# ir_remote_v3.net
KiCad netlist of a schematic drawn in EAGLE
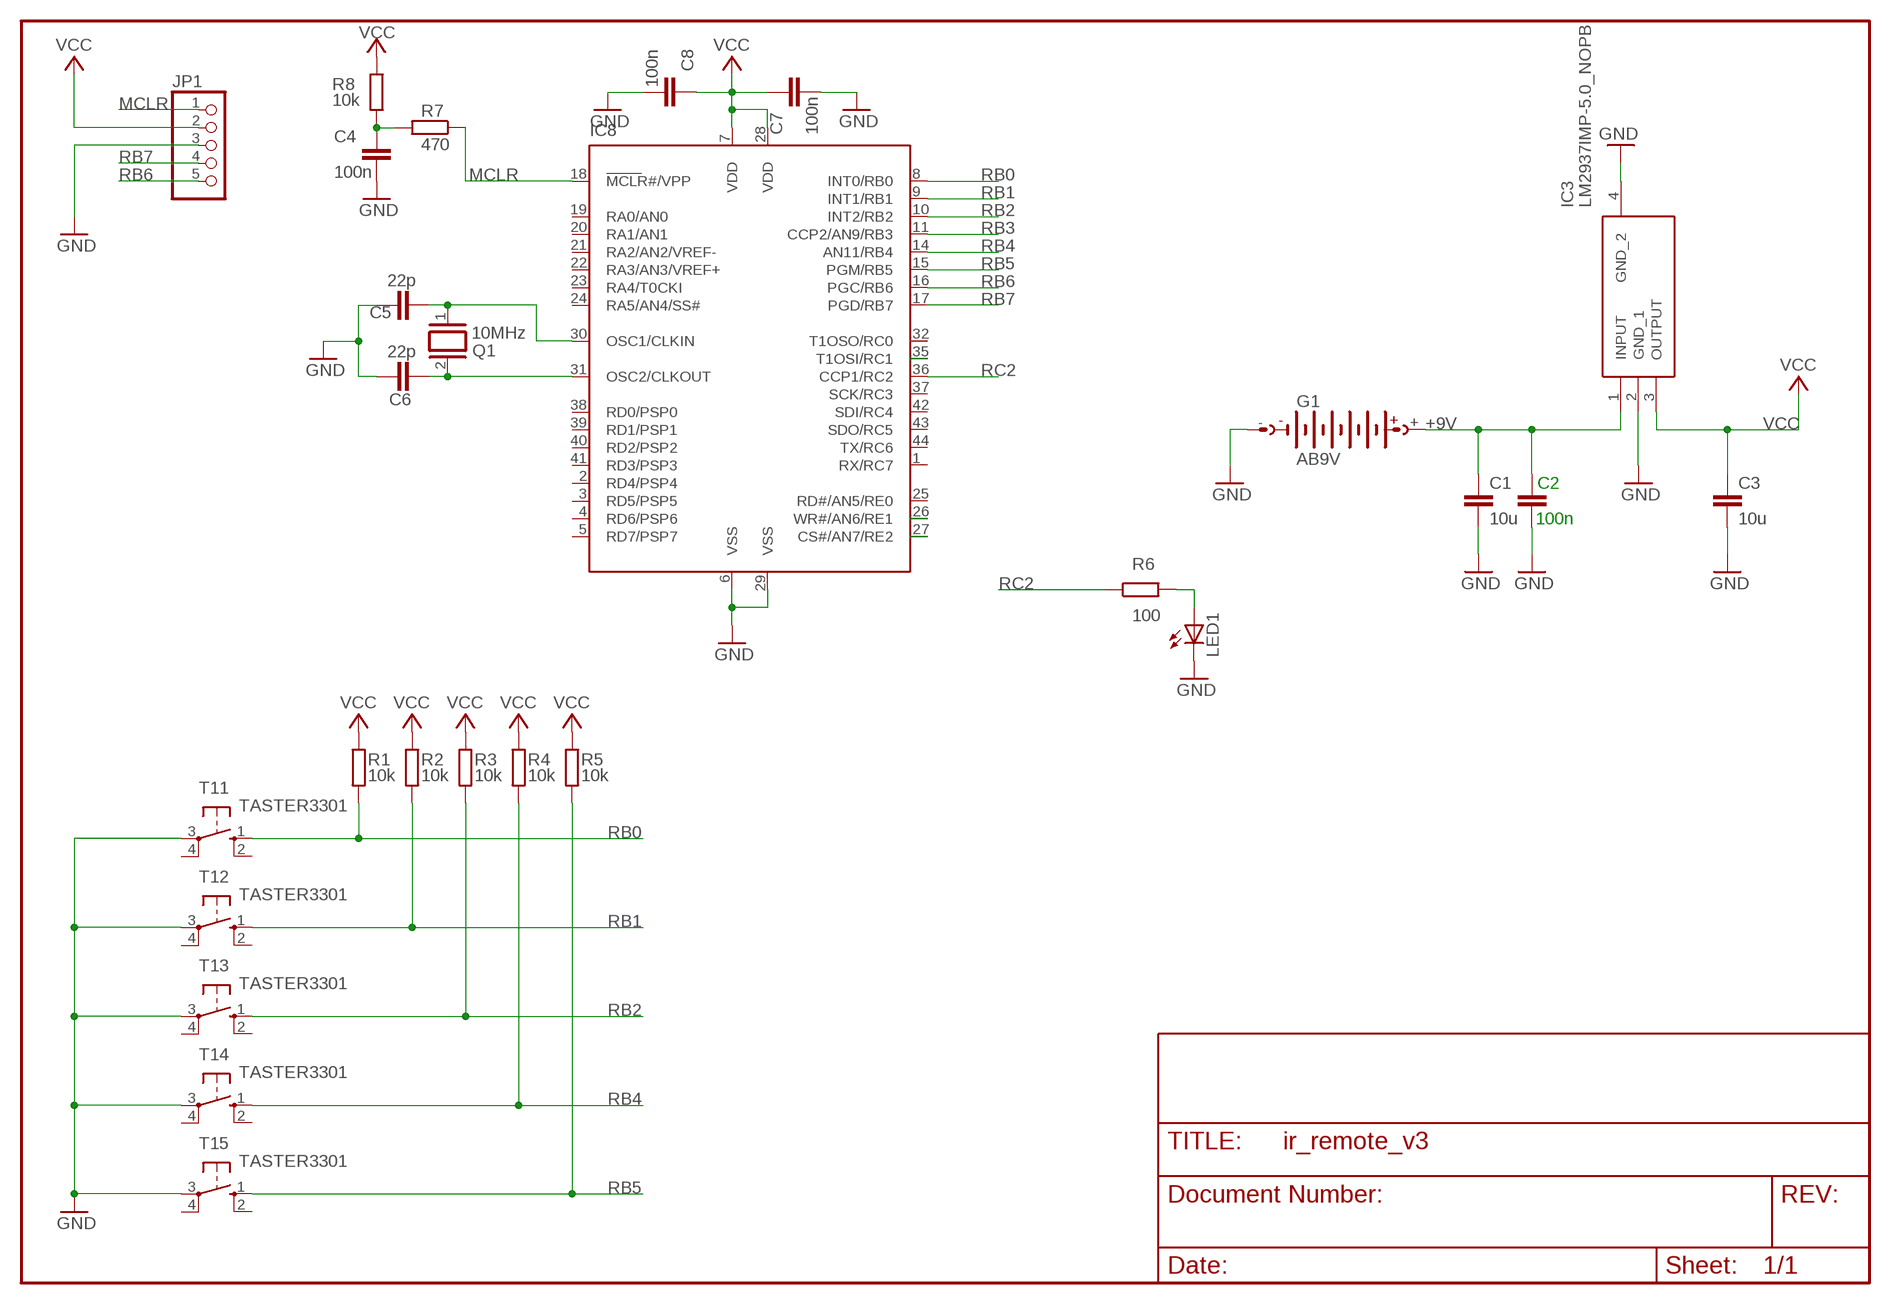
[diagram p0: schematic, sheet 1]

(export (version "E")
  (design (tool "Eeschema 10.0.6"))
  (components
    (comp (ref "C1")
      (value "10u")
      (footprint "eagle-import:C0805")
      (libsource (lib "eagle-import") (part "C-EUC0805"))
    )
    (comp (ref "C2")
      (value "100n")
      (footprint "eagle-import:C0805")
      (libsource (lib "eagle-import") (part "rcl_416_C-EUC0805"))
    )
    (comp (ref "C3")
      (value "10u")
      (footprint "eagle-import:C0805")
      (libsource (lib "eagle-import") (part "C-EUC0805"))
    )
    (comp (ref "C4")
      (value "100n")
      (footprint "eagle-import:C0805")
      (libsource (lib "eagle-import") (part "C-EUC0805"))
    )
    (comp (ref "C5")
      (value "22p")
      (footprint "eagle-import:C0603_WE")
      (libsource (lib "eagle-import") (part "C-EUC0603_WE"))
    )
    (comp (ref "C6")
      (value "22p")
      (footprint "eagle-import:C0603_WE")
      (libsource (lib "eagle-import") (part "C-EUC0603_WE"))
    )
    (comp (ref "C7")
      (value "100n")
      (footprint "eagle-import:C0805")
      (libsource (lib "eagle-import") (part "C-EUC0805"))
    )
    (comp (ref "C8")
      (value "100n")
      (footprint "eagle-import:C0805")
      (libsource (lib "eagle-import") (part "C-EUC0805"))
    )
    (comp (ref "G1")
      (value "AB9V")
      (footprint "eagle-import:AB9V")
      (libsource (lib "eagle-import") (part "AB9V"))
    )
    (comp (ref "IC3")
      (value "LM2937IMP-5.0_NOPB")
      (footprint "eagle-import:SOT230P700X180-4N")
      (fields (field (name "MANUFACTURER_PART_NUMBER") "LM2937IMP-5.0/NOPB"))
      (libsource (lib "eagle-import") (part "LM2937IMP-5.0_NOPB"))
    )
    (comp (ref "IC8")
      (value "PIC18F4520")
      (footprint "eagle-import:TQFP44")
      (libsource (lib "eagle-import") (part "PIC18F4520"))
    )
    (comp (ref "JP1")
      (value "PINHD-1X5")
      (footprint "eagle-import:1X05")
      (libsource (lib "eagle-import") (part "PINHD-1X5"))
    )
    (comp (ref "LED1")
      (value "LED5MM")
      (footprint "eagle-import:LED5MM")
      (libsource (lib "eagle-import") (part "LED5MM"))
    )
    (comp (ref "Q1")
      (value "10MHz")
      (footprint "eagle-import:QUARZ_HC5032_2")
      (libsource (lib "eagle-import") (part "XTAL_HC5032"))
    )
    (comp (ref "R1")
      (value "10k")
      (footprint "eagle-import:M0805")
      (libsource (lib "eagle-import") (part "R-EU_M0805"))
    )
    (comp (ref "R2")
      (value "10k")
      (footprint "eagle-import:M0805")
      (libsource (lib "eagle-import") (part "R-EU_M0805"))
    )
    (comp (ref "R3")
      (value "10k")
      (footprint "eagle-import:M0805")
      (libsource (lib "eagle-import") (part "R-EU_M0805"))
    )
    (comp (ref "R4")
      (value "10k")
      (footprint "eagle-import:M0805")
      (libsource (lib "eagle-import") (part "R-EU_M0805"))
    )
    (comp (ref "R5")
      (value "10k")
      (footprint "eagle-import:M0805")
      (libsource (lib "eagle-import") (part "R-EU_M0805"))
    )
    (comp (ref "R6")
      (value "100")
      (footprint "eagle-import:M0805")
      (libsource (lib "eagle-import") (part "R-EU_M0805"))
    )
    (comp (ref "R7")
      (value "470")
      (footprint "eagle-import:M0805")
      (libsource (lib "eagle-import") (part "R-EU_M0805"))
    )
    (comp (ref "R8")
      (value "10k")
      (footprint "eagle-import:M0805")
      (libsource (lib "eagle-import") (part "R-EU_M0805"))
    )
    (comp (ref "T11")
      (value "TASTER3301")
      (footprint "eagle-import:TASTER3301")
      (libsource (lib "eagle-import") (part "TASTER3301"))
    )
    (comp (ref "T12")
      (value "TASTER3301")
      (footprint "eagle-import:TASTER3301")
      (libsource (lib "eagle-import") (part "TASTER3301"))
    )
    (comp (ref "T13")
      (value "TASTER3301")
      (footprint "eagle-import:TASTER3301")
      (libsource (lib "eagle-import") (part "TASTER3301"))
    )
    (comp (ref "T14")
      (value "TASTER3301")
      (footprint "eagle-import:TASTER3301")
      (libsource (lib "eagle-import") (part "TASTER3301"))
    )
    (comp (ref "T15")
      (value "TASTER3301")
      (footprint "eagle-import:TASTER3301")
      (libsource (lib "eagle-import") (part "TASTER3301"))
    )
  )
  (nets
    (net (code "1") (name "/+9V") (class "Default")
      (node (ref "C1") (pin "1") (pinfunction "1_1") (pintype "passive"))
      (node (ref "C2") (pin "1") (pinfunction "1_1") (pintype "passive"))
      (node (ref "G1") (pin "+") (pinfunction "+_+") (pintype "passive"))
      (node (ref "IC3") (pin "1") (pinfunction "INPUT_1") (pintype "bidirectional"))
    )
    (net (code "2") (name "/MCLR") (class "Default")
      (node (ref "IC8") (pin "18") (pinfunction "MCLR#/VPP_18") (pintype "input"))
      (node (ref "JP1") (pin "1") (pinfunction "1_1") (pintype "passive"))
      (node (ref "R7") (pin "1") (pinfunction "1_1") (pintype "passive"))
    )
    (net (code "3") (name "/RB0") (class "Default")
      (node (ref "IC8") (pin "8") (pinfunction "INT0/RB0_8") (pintype "bidirectional"))
      (node (ref "R1") (pin "2") (pinfunction "2_2") (pintype "passive"))
      (node (ref "T11") (pin "1") (pinfunction "S_1") (pintype "passive"))
    )
    (net (code "4") (name "/RB1") (class "Default")
      (node (ref "IC8") (pin "35") (pinfunction "T1OSI/RC1_35") (pintype "bidirectional"))
      (node (ref "IC8") (pin "9") (pinfunction "INT1/RB1_9") (pintype "bidirectional"))
      (node (ref "R2") (pin "2") (pinfunction "2_2") (pintype "passive"))
      (node (ref "T12") (pin "1") (pinfunction "S_1") (pintype "passive"))
    )
    (net (code "5") (name "/RB2") (class "Default")
      (node (ref "IC8") (pin "10") (pinfunction "INT2/RB2_10") (pintype "bidirectional"))
      (node (ref "IC8") (pin "32") (pinfunction "T1OSO/RC0_32") (pintype "bidirectional"))
      (node (ref "R3") (pin "2") (pinfunction "2_2") (pintype "passive"))
      (node (ref "T13") (pin "1") (pinfunction "S_1") (pintype "passive"))
    )
    (net (code "6") (name "/RB3") (class "Default")
      (node (ref "IC8") (pin "11") (pinfunction "CCP2/AN9/RB3_11") (pintype "bidirectional"))
    )
    (net (code "7") (name "/RB4") (class "Default")
      (node (ref "IC8") (pin "14") (pinfunction "AN11/RB4_14") (pintype "bidirectional"))
      (node (ref "R4") (pin "2") (pinfunction "2_2") (pintype "passive"))
      (node (ref "T14") (pin "1") (pinfunction "S_1") (pintype "passive"))
    )
    (net (code "8") (name "/RB5") (class "Default")
      (node (ref "IC8") (pin "15") (pinfunction "PGM/RB5_15") (pintype "bidirectional"))
      (node (ref "R5") (pin "2") (pinfunction "2_2") (pintype "passive"))
      (node (ref "T15") (pin "1") (pinfunction "S_1") (pintype "passive"))
    )
    (net (code "9") (name "/RB6") (class "Default")
      (node (ref "IC8") (pin "16") (pinfunction "PGC/RB6_16") (pintype "bidirectional"))
      (node (ref "JP1") (pin "5") (pinfunction "5_5") (pintype "passive"))
    )
    (net (code "10") (name "/RB7") (class "Default")
      (node (ref "IC8") (pin "17") (pinfunction "PGD/RB7_17") (pintype "bidirectional"))
      (node (ref "JP1") (pin "4") (pinfunction "4_4") (pintype "passive"))
    )
    (net (code "11") (name "/RC2") (class "Default")
      (node (ref "IC8") (pin "36") (pinfunction "CCP1/RC2_36") (pintype "bidirectional"))
      (node (ref "R6") (pin "1") (pinfunction "1_1") (pintype "passive"))
    )
    (net (code "12") (name "GND") (class "Default")
      (node (ref "C1") (pin "2") (pinfunction "2_2") (pintype "passive"))
      (node (ref "C2") (pin "2") (pinfunction "2_2") (pintype "passive"))
      (node (ref "C3") (pin "2") (pinfunction "2_2") (pintype "passive"))
      (node (ref "C4") (pin "2") (pinfunction "2_2") (pintype "passive"))
      (node (ref "C5") (pin "1") (pinfunction "1_1") (pintype "passive"))
      (node (ref "C6") (pin "1") (pinfunction "1_1") (pintype "passive"))
      (node (ref "C7") (pin "2") (pinfunction "2_2") (pintype "passive"))
      (node (ref "C8") (pin "2") (pinfunction "2_2") (pintype "passive"))
      (node (ref "G1") (pin "-") (pinfunction "-_-") (pintype "passive"))
      (node (ref "IC3") (pin "2") (pinfunction "GND_1_2") (pintype "bidirectional"))
      (node (ref "IC3") (pin "4") (pinfunction "GND_2_4") (pintype "bidirectional"))
      (node (ref "IC8") (pin "29") (pinfunction "VSS_29") (pintype "bidirectional"))
      (node (ref "IC8") (pin "6") (pinfunction "VSS_6") (pintype "bidirectional"))
      (node (ref "JP1") (pin "3") (pinfunction "3_3") (pintype "passive"))
      (node (ref "LED1") (pin "K") (pinfunction "C_K") (pintype "passive"))
      (node (ref "T11") (pin "3") (pinfunction "P_3") (pintype "passive"))
      (node (ref "T12") (pin "3") (pinfunction "P_3") (pintype "passive"))
      (node (ref "T13") (pin "3") (pinfunction "P_3") (pintype "passive"))
      (node (ref "T14") (pin "3") (pinfunction "P_3") (pintype "passive"))
      (node (ref "T15") (pin "3") (pinfunction "P_3") (pintype "passive"))
    )
    (net (code "13") (name "Net-(C4-Pad1)") (class "Default")
      (node (ref "C4") (pin "1") (pinfunction "1_1") (pintype "passive"))
      (node (ref "R7") (pin "2") (pinfunction "2_2") (pintype "passive"))
      (node (ref "R8") (pin "2") (pinfunction "2_2") (pintype "passive"))
    )
    (net (code "14") (name "Net-(IC8-OSC1{slash}CLKIN)") (class "Default")
      (node (ref "C5") (pin "2") (pinfunction "2_2") (pintype "passive"))
      (node (ref "IC8") (pin "30") (pinfunction "OSC1/CLKIN_30") (pintype "input"))
      (node (ref "Q1") (pin "1") (pinfunction "1_1") (pintype "passive"))
    )
    (net (code "15") (name "Net-(IC8-OSC2{slash}CLKOUT)") (class "Default")
      (node (ref "C6") (pin "2") (pinfunction "2_2") (pintype "passive"))
      (node (ref "IC8") (pin "31") (pinfunction "OSC2/CLKOUT_31") (pintype "output"))
      (node (ref "Q1") (pin "2") (pinfunction "2_2") (pintype "passive"))
    )
    (net (code "16") (name "Net-(LED1-PadA)") (class "Default")
      (node (ref "LED1") (pin "A") (pinfunction "A_A") (pintype "passive"))
      (node (ref "R6") (pin "2") (pinfunction "2_2") (pintype "passive"))
    )
    (net (code "17") (name "VCC") (class "Default")
      (node (ref "C3") (pin "1") (pinfunction "1_1") (pintype "passive"))
      (node (ref "C7") (pin "1") (pinfunction "1_1") (pintype "passive"))
      (node (ref "C8") (pin "1") (pinfunction "1_1") (pintype "passive"))
      (node (ref "IC3") (pin "3") (pinfunction "OUTPUT_3") (pintype "bidirectional"))
      (node (ref "IC8") (pin "28") (pinfunction "VDD_28") (pintype "bidirectional"))
      (node (ref "IC8") (pin "7") (pinfunction "VDD_7") (pintype "bidirectional"))
      (node (ref "JP1") (pin "2") (pinfunction "2_2") (pintype "passive"))
      (node (ref "R1") (pin "1") (pinfunction "1_1") (pintype "passive"))
      (node (ref "R2") (pin "1") (pinfunction "1_1") (pintype "passive"))
      (node (ref "R3") (pin "1") (pinfunction "1_1") (pintype "passive"))
      (node (ref "R4") (pin "1") (pinfunction "1_1") (pintype "passive"))
      (node (ref "R5") (pin "1") (pinfunction "1_1") (pintype "passive"))
      (node (ref "R8") (pin "1") (pinfunction "1_1") (pintype "passive"))
    )
    (net (code "18") (name "unconnected-(IC8-CS#{slash}AN7{slash}RE2-Pad27)") (class "Default")
      (node (ref "IC8") (pin "27") (pinfunction "CS#/AN7/RE2_27") (pintype "bidirectional"))
    )
    (net (code "19") (name "unconnected-(IC8-RA0{slash}AN0-Pad19)") (class "Default")
      (node (ref "IC8") (pin "19") (pinfunction "RA0/AN0_19") (pintype "bidirectional"))
    )
    (net (code "20") (name "unconnected-(IC8-RA1{slash}AN1-Pad20)") (class "Default")
      (node (ref "IC8") (pin "20") (pinfunction "RA1/AN1_20") (pintype "bidirectional"))
    )
    (net (code "21") (name "unconnected-(IC8-RA2{slash}AN2{slash}VREF--Pad21)") (class "Default")
      (node (ref "IC8") (pin "21") (pinfunction "RA2/AN2/VREF-_21") (pintype "bidirectional"))
    )
    (net (code "22") (name "unconnected-(IC8-RA3{slash}AN3{slash}VREF+-Pad22)") (class "Default")
      (node (ref "IC8") (pin "22") (pinfunction "RA3/AN3/VREF+_22") (pintype "bidirectional"))
    )
    (net (code "23") (name "unconnected-(IC8-RA4{slash}T0CKI-Pad23)") (class "Default")
      (node (ref "IC8") (pin "23") (pinfunction "RA4/T0CKI_23") (pintype "bidirectional"))
    )
    (net (code "24") (name "unconnected-(IC8-RA5{slash}AN4{slash}SS#-Pad24)") (class "Default")
      (node (ref "IC8") (pin "24") (pinfunction "RA5/AN4/SS#_24") (pintype "bidirectional"))
    )
    (net (code "25") (name "unconnected-(IC8-RD#{slash}AN5{slash}RE0-Pad25)") (class "Default")
      (node (ref "IC8") (pin "25") (pinfunction "RD#/AN5/RE0_25") (pintype "bidirectional"))
    )
    (net (code "26") (name "unconnected-(IC8-RD0{slash}PSP0-Pad38)") (class "Default")
      (node (ref "IC8") (pin "38") (pinfunction "RD0/PSP0_38") (pintype "bidirectional"))
    )
    (net (code "27") (name "unconnected-(IC8-RD1{slash}PSP1-Pad39)") (class "Default")
      (node (ref "IC8") (pin "39") (pinfunction "RD1/PSP1_39") (pintype "bidirectional"))
    )
    (net (code "28") (name "unconnected-(IC8-RD2{slash}PSP2-Pad40)") (class "Default")
      (node (ref "IC8") (pin "40") (pinfunction "RD2/PSP2_40") (pintype "bidirectional"))
    )
    (net (code "29") (name "unconnected-(IC8-RD3{slash}PSP3-Pad41)") (class "Default")
      (node (ref "IC8") (pin "41") (pinfunction "RD3/PSP3_41") (pintype "bidirectional"))
    )
    (net (code "30") (name "unconnected-(IC8-RD4{slash}PSP4-Pad2)") (class "Default")
      (node (ref "IC8") (pin "2") (pinfunction "RD4/PSP4_2") (pintype "bidirectional"))
    )
    (net (code "31") (name "unconnected-(IC8-RD5{slash}PSP5-Pad3)") (class "Default")
      (node (ref "IC8") (pin "3") (pinfunction "RD5/PSP5_3") (pintype "bidirectional"))
    )
    (net (code "32") (name "unconnected-(IC8-RD6{slash}PSP6-Pad4)") (class "Default")
      (node (ref "IC8") (pin "4") (pinfunction "RD6/PSP6_4") (pintype "bidirectional"))
    )
    (net (code "33") (name "unconnected-(IC8-RD7{slash}PSP7-Pad5)") (class "Default")
      (node (ref "IC8") (pin "5") (pinfunction "RD7/PSP7_5") (pintype "bidirectional"))
    )
    (net (code "34") (name "unconnected-(IC8-RX{slash}RC7-Pad1)") (class "Default")
      (node (ref "IC8") (pin "1") (pinfunction "RX/RC7_1") (pintype "bidirectional"))
    )
    (net (code "35") (name "unconnected-(IC8-SCK{slash}RC3-Pad37)") (class "Default")
      (node (ref "IC8") (pin "37") (pinfunction "SCK/RC3_37") (pintype "bidirectional"))
    )
    (net (code "36") (name "unconnected-(IC8-SDI{slash}RC4-Pad42)") (class "Default")
      (node (ref "IC8") (pin "42") (pinfunction "SDI/RC4_42") (pintype "bidirectional"))
    )
    (net (code "37") (name "unconnected-(IC8-SDO{slash}RC5-Pad43)") (class "Default")
      (node (ref "IC8") (pin "43") (pinfunction "SDO/RC5_43") (pintype "bidirectional"))
    )
    (net (code "38") (name "unconnected-(IC8-TX{slash}RC6-Pad44)") (class "Default")
      (node (ref "IC8") (pin "44") (pinfunction "TX/RC6_44") (pintype "bidirectional"))
    )
    (net (code "39") (name "unconnected-(IC8-WR#{slash}AN6{slash}RE1-Pad26)") (class "Default")
      (node (ref "IC8") (pin "26") (pinfunction "WR#/AN6/RE1_26") (pintype "bidirectional"))
    )
    (net (code "40") (name "unconnected-(T11-P1-Pad4)") (class "Default")
      (node (ref "T11") (pin "4") (pinfunction "P1_4") (pintype "passive"))
    )
    (net (code "41") (name "unconnected-(T11-S1-Pad2)") (class "Default")
      (node (ref "T11") (pin "2") (pinfunction "S1_2") (pintype "passive"))
    )
    (net (code "42") (name "unconnected-(T12-P1-Pad4)") (class "Default")
      (node (ref "T12") (pin "4") (pinfunction "P1_4") (pintype "passive"))
    )
    (net (code "43") (name "unconnected-(T12-S1-Pad2)") (class "Default")
      (node (ref "T12") (pin "2") (pinfunction "S1_2") (pintype "passive"))
    )
    (net (code "44") (name "unconnected-(T13-P1-Pad4)") (class "Default")
      (node (ref "T13") (pin "4") (pinfunction "P1_4") (pintype "passive"))
    )
    (net (code "45") (name "unconnected-(T13-S1-Pad2)") (class "Default")
      (node (ref "T13") (pin "2") (pinfunction "S1_2") (pintype "passive"))
    )
    (net (code "46") (name "unconnected-(T14-P1-Pad4)") (class "Default")
      (node (ref "T14") (pin "4") (pinfunction "P1_4") (pintype "passive"))
    )
    (net (code "47") (name "unconnected-(T14-S1-Pad2)") (class "Default")
      (node (ref "T14") (pin "2") (pinfunction "S1_2") (pintype "passive"))
    )
    (net (code "48") (name "unconnected-(T15-P1-Pad4)") (class "Default")
      (node (ref "T15") (pin "4") (pinfunction "P1_4") (pintype "passive"))
    )
    (net (code "49") (name "unconnected-(T15-S1-Pad2)") (class "Default")
      (node (ref "T15") (pin "2") (pinfunction "S1_2") (pintype "passive"))
    )
  )
)
